# Top_Level.net
KiCad netlist of a schematic drawn in Altium Designer
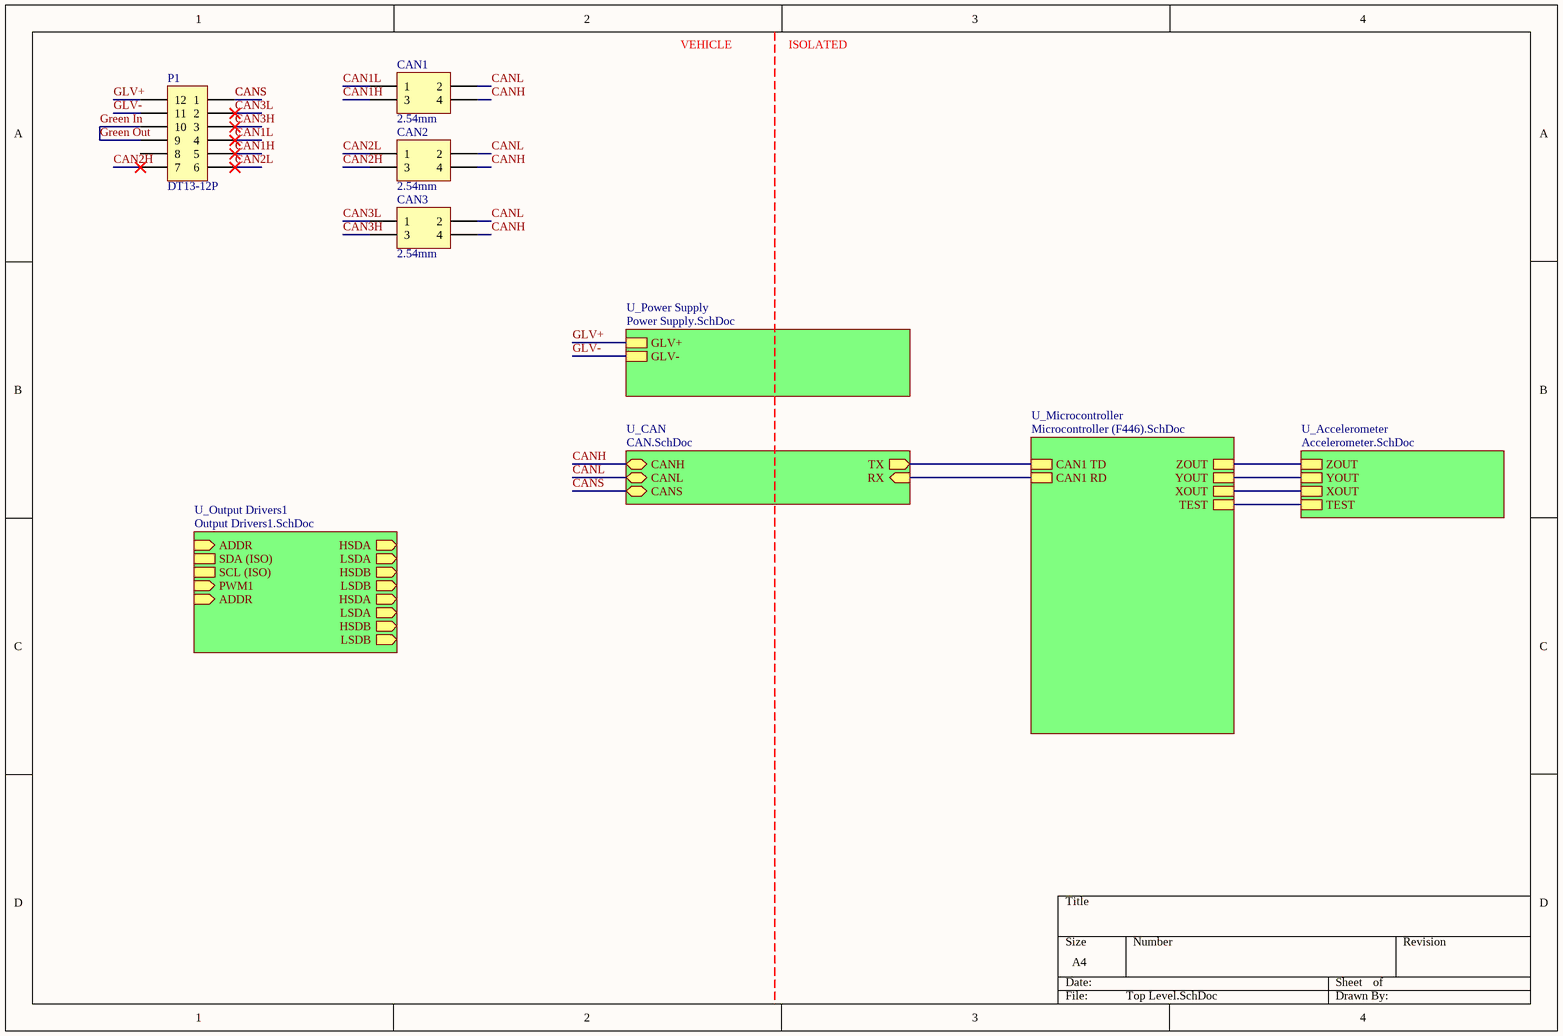
[diagram p0: Top Level.SchDoc]

(export (version "E")
  (design (tool "Eeschema 10.0.6"))
  (components
    (comp (ref "CAN1")
      (value "2.54mm")
      (footprint "TH 2.54mm Header 2x2")
      (fields (field (name "PART NUMBER") "TH 2.54mm Header 2x2") (field (name "CONTACT") "NA"))
      (libsource (lib "ts_20-standard-connectors") (part "Header 2x2"))
    )
    (comp (ref "CAN2")
      (value "2.54mm")
      (footprint "TH 2.54mm Header 2x2")
      (fields (field (name "PART NUMBER") "TH 2.54mm Header 2x2") (field (name "CONTACT") "NA"))
      (libsource (lib "ts_20-standard-connectors") (part "Header 2x2"))
    )
    (comp (ref "CAN3")
      (value "2.54mm")
      (footprint "TH 2.54mm Header 2x2")
      (fields (field (name "PART NUMBER") "TH 2.54mm Header 2x2") (field (name "CONTACT") "NA"))
      (libsource (lib "ts_20-standard-connectors") (part "Header 2x2"))
    )
    (comp (ref "P1")
      (value "DT13-12P")
      (footprint "DT13-12P")
      (fields (field (name "DIGIKEY PART NUMBER") "1734-1451-ND") (field (name "CONTACT") "Nickel"))
      (libsource (lib "ts_20-standard-connectors") (part "DT13-12P"))
    )
  )
  (nets
    (net (code "4") (name "/CAN1H") (class "Default")
      (node (ref "CAN1") (pin "3") (pinfunction "3_3") (pintype "passive"))
      (node (ref "P1") (pin "5") (pinfunction "5_5") (pintype "power_in"))
    )
    (net (code "5") (name "/CAN1L") (class "Default")
      (node (ref "CAN1") (pin "1") (pinfunction "1_1") (pintype "passive"))
      (node (ref "P1") (pin "4") (pinfunction "4_4") (pintype "power_in"))
    )
    (net (code "6") (name "/CAN2H") (class "Default")
      (node (ref "CAN2") (pin "3") (pinfunction "3_3") (pintype "passive"))
      (node (ref "P1") (pin "7") (pinfunction "7_7") (pintype "passive"))
    )
    (net (code "7") (name "/CAN2L") (class "Default")
      (node (ref "CAN2") (pin "1") (pinfunction "1_1") (pintype "passive"))
      (node (ref "P1") (pin "6") (pinfunction "6_6") (pintype "power_in"))
    )
    (net (code "8") (name "/CAN3H") (class "Default")
      (node (ref "CAN3") (pin "3") (pinfunction "3_3") (pintype "passive"))
      (node (ref "P1") (pin "3") (pinfunction "3_3") (pintype "power_in"))
    )
    (net (code "9") (name "/CAN3L") (class "Default")
      (node (ref "CAN3") (pin "1") (pinfunction "1_1") (pintype "passive"))
      (node (ref "P1") (pin "2") (pinfunction "2_2") (pintype "power_in"))
    )
    (net (code "10") (name "/CANH") (class "Default")
      (node (ref "CAN1") (pin "4") (pinfunction "4_4") (pintype "passive"))
      (node (ref "CAN2") (pin "4") (pinfunction "4_4") (pintype "passive"))
      (node (ref "CAN3") (pin "4") (pinfunction "4_4") (pintype "passive"))
    )
    (net (code "11") (name "/CANL") (class "Default")
      (node (ref "CAN1") (pin "2") (pinfunction "2_2") (pintype "passive"))
      (node (ref "CAN2") (pin "2") (pinfunction "2_2") (pintype "passive"))
      (node (ref "CAN3") (pin "2") (pinfunction "2_2") (pintype "passive"))
    )
    (net (code "12") (name "/CANS") (class "Default")
      (node (ref "P1") (pin "1") (pinfunction "1_1") (pintype "power_in"))
    )
    (net (code "13") (name "/GLV+") (class "Default")
      (node (ref "P1") (pin "12") (pinfunction "12_12") (pintype "passive"))
    )
    (net (code "14") (name "/GLV-") (class "Default")
      (node (ref "P1") (pin "11") (pinfunction "11_11") (pintype "passive"))
    )
    (net (code "15") (name "/Green In") (class "Default")
      (node (ref "P1") (pin "10") (pinfunction "10_10") (pintype "passive"))
      (node (ref "P1") (pin "9") (pinfunction "9_9") (pintype "passive"))
    )
    (net (code "32") (name "unconnected-(P1-Pad8)") (class "Default")
      (node (ref "P1") (pin "8") (pinfunction "8_8") (pintype "passive"))
    )
  )
)
